# OptodeConnectors.net
KiCad netlist of a schematic drawn in Altium Designer
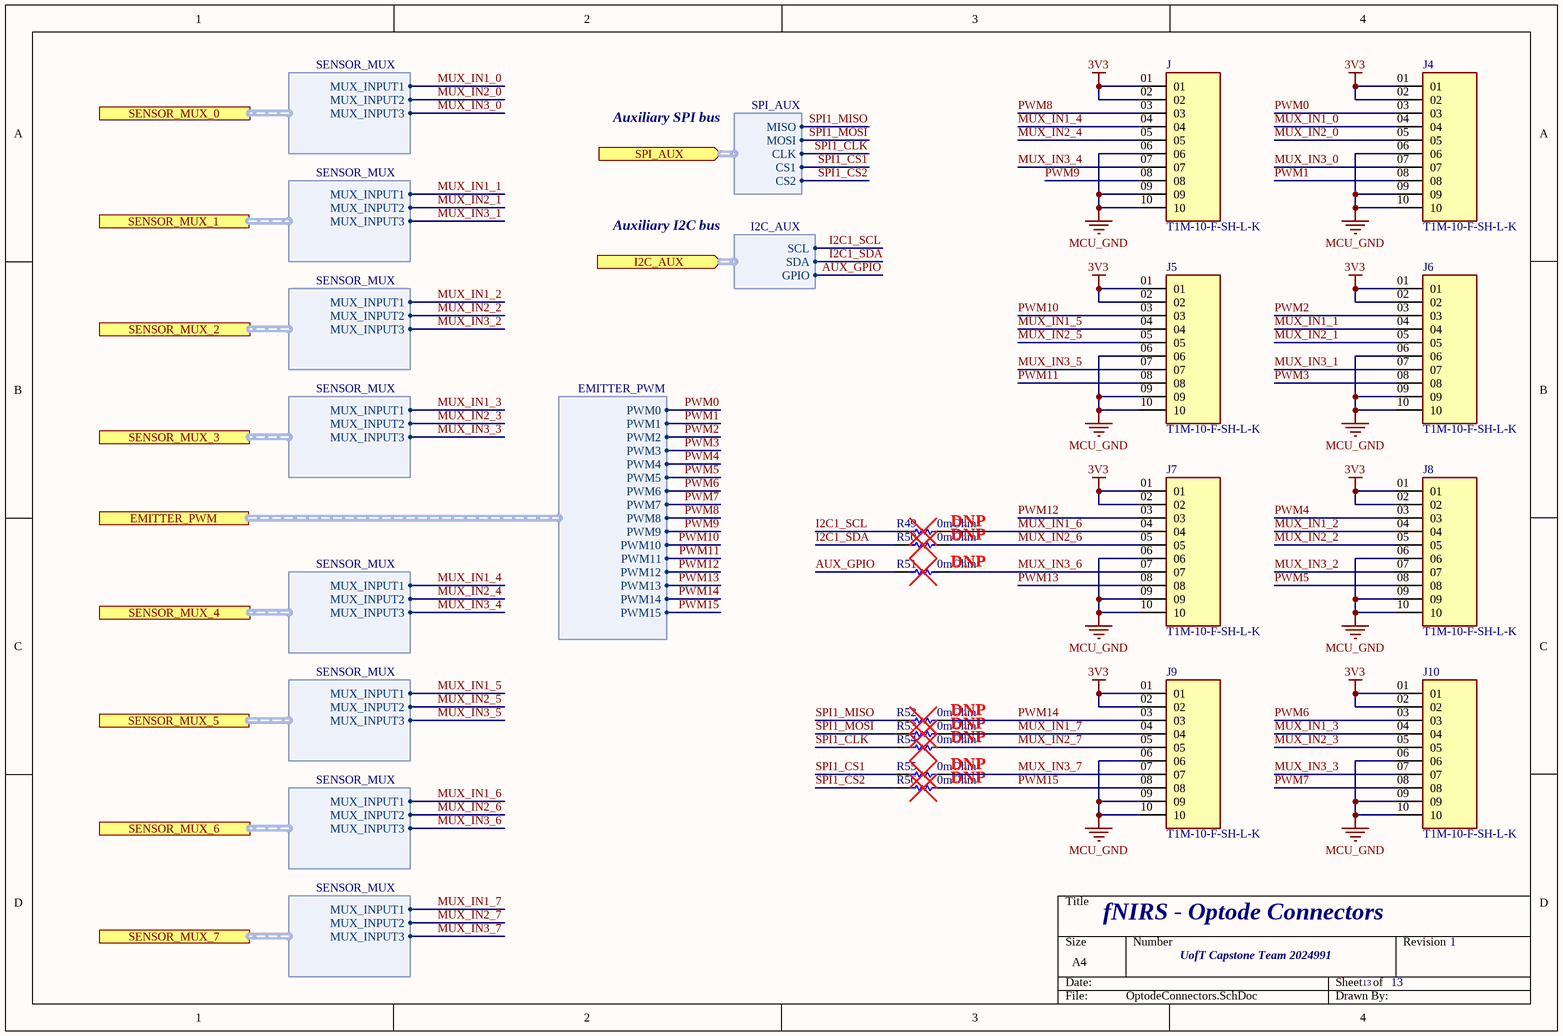
[diagram p0: OptodeConnectors.SchDoc]

(export (version "E")
  (design (tool "Eeschema 10.0.6"))
  (components
    (comp (ref "J")
      (value "T1M-10-F-SH-L-K")
      (footprint "SAMTEC_T1M-10-F-SH-L-K")
      (fields (field (name "MF") "Samtec"))
      (libsource (lib "Schlib2") (part "T1M-10-F-SH-L-K"))
    )
    (comp (ref "J4")
      (value "T1M-10-F-SH-L-K")
      (footprint "SAMTEC_T1M-10-F-SH-L-K")
      (fields (field (name "MF") "Samtec"))
      (libsource (lib "Schlib2") (part "T1M-10-F-SH-L-K"))
    )
    (comp (ref "J5")
      (value "T1M-10-F-SH-L-K")
      (footprint "SAMTEC_T1M-10-F-SH-L-K")
      (fields (field (name "MF") "Samtec"))
      (libsource (lib "Schlib2") (part "T1M-10-F-SH-L-K"))
    )
    (comp (ref "J6")
      (value "T1M-10-F-SH-L-K")
      (footprint "SAMTEC_T1M-10-F-SH-L-K")
      (fields (field (name "MF") "Samtec"))
      (libsource (lib "Schlib2") (part "T1M-10-F-SH-L-K"))
    )
    (comp (ref "J7")
      (value "T1M-10-F-SH-L-K")
      (footprint "SAMTEC_T1M-10-F-SH-L-K")
      (fields (field (name "MF") "Samtec"))
      (libsource (lib "Schlib2") (part "T1M-10-F-SH-L-K"))
    )
    (comp (ref "J8")
      (value "T1M-10-F-SH-L-K")
      (footprint "SAMTEC_T1M-10-F-SH-L-K")
      (fields (field (name "MF") "Samtec"))
      (libsource (lib "Schlib2") (part "T1M-10-F-SH-L-K"))
    )
    (comp (ref "J9")
      (value "T1M-10-F-SH-L-K")
      (footprint "SAMTEC_T1M-10-F-SH-L-K")
      (fields (field (name "MF") "Samtec"))
      (libsource (lib "Schlib2") (part "T1M-10-F-SH-L-K"))
    )
    (comp (ref "J10")
      (value "T1M-10-F-SH-L-K")
      (footprint "SAMTEC_T1M-10-F-SH-L-K")
      (fields (field (name "MF") "Samtec"))
      (libsource (lib "Schlib2") (part "T1M-10-F-SH-L-K"))
    )
    (comp (ref "R49")
      (value "RC0603JR-070RL")
      (footprint "RESC1608X55X25ML10T15")
      (description "Chip Resistor, 0 Ohm, +/- 5%, 0.1 W, -55 to 155 degC, 0603 (1608 Metric), RoHS, Tape and Reel")
      (fields
        (field (name "TOLERANCE") "5%")
        (field (name "RESISTANCE") "0mOhm")
        (field (name "MANUFACTURER") "Yageo")
      )
      (libsource (lib "Altium Content Vault") (part "RES-2"))
    )
    (comp (ref "R50")
      (value "RC0603JR-070RL")
      (footprint "RESC1608X55X25ML10T15")
      (description "Chip Resistor, 0 Ohm, +/- 5%, 0.1 W, -55 to 155 degC, 0603 (1608 Metric), RoHS, Tape and Reel")
      (fields
        (field (name "TOLERANCE") "5%")
        (field (name "RESISTANCE") "0mOhm")
        (field (name "MANUFACTURER") "Yageo")
      )
      (libsource (lib "Altium Content Vault") (part "RES-2"))
    )
    (comp (ref "R51")
      (value "RC0603JR-070RL")
      (footprint "RESC1608X55X25ML10T15")
      (description "Chip Resistor, 0 Ohm, +/- 5%, 0.1 W, -55 to 155 degC, 0603 (1608 Metric), RoHS, Tape and Reel")
      (fields
        (field (name "TOLERANCE") "5%")
        (field (name "RESISTANCE") "0mOhm")
        (field (name "MANUFACTURER") "Yageo")
      )
      (libsource (lib "Altium Content Vault") (part "RES-2"))
    )
    (comp (ref "R52")
      (value "RC0603JR-070RL")
      (footprint "RESC1608X55X25ML10T15")
      (description "Chip Resistor, 0 Ohm, +/- 5%, 0.1 W, -55 to 155 degC, 0603 (1608 Metric), RoHS, Tape and Reel")
      (fields
        (field (name "TOLERANCE") "5%")
        (field (name "RESISTANCE") "0mOhm")
        (field (name "MANUFACTURER") "Yageo")
      )
      (libsource (lib "Altium Content Vault") (part "RES-2"))
    )
    (comp (ref "R53")
      (value "RC0603JR-070RL")
      (footprint "RESC1608X55X25ML10T15")
      (description "Chip Resistor, 0 Ohm, +/- 5%, 0.1 W, -55 to 155 degC, 0603 (1608 Metric), RoHS, Tape and Reel")
      (fields
        (field (name "TOLERANCE") "5%")
        (field (name "RESISTANCE") "0mOhm")
        (field (name "MANUFACTURER") "Yageo")
      )
      (libsource (lib "Altium Content Vault") (part "RES-2"))
    )
    (comp (ref "R54")
      (value "RC0603JR-070RL")
      (footprint "RESC1608X55X25ML10T15")
      (description "Chip Resistor, 0 Ohm, +/- 5%, 0.1 W, -55 to 155 degC, 0603 (1608 Metric), RoHS, Tape and Reel")
      (fields
        (field (name "TOLERANCE") "5%")
        (field (name "RESISTANCE") "0mOhm")
        (field (name "MANUFACTURER") "Yageo")
      )
      (libsource (lib "Altium Content Vault") (part "RES-2"))
    )
    (comp (ref "R55")
      (value "RC0603JR-070RL")
      (footprint "RESC1608X55X25ML10T15")
      (description "Chip Resistor, 0 Ohm, +/- 5%, 0.1 W, -55 to 155 degC, 0603 (1608 Metric), RoHS, Tape and Reel")
      (fields
        (field (name "TOLERANCE") "5%")
        (field (name "RESISTANCE") "0mOhm")
        (field (name "MANUFACTURER") "Yageo")
      )
      (libsource (lib "Altium Content Vault") (part "RES-2"))
    )
    (comp (ref "R56")
      (value "RC0603JR-070RL")
      (footprint "RESC1608X55X25ML10T15")
      (description "Chip Resistor, 0 Ohm, +/- 5%, 0.1 W, -55 to 155 degC, 0603 (1608 Metric), RoHS, Tape and Reel")
      (fields
        (field (name "TOLERANCE") "5%")
        (field (name "RESISTANCE") "0mOhm")
        (field (name "MANUFACTURER") "Yageo")
      )
      (libsource (lib "Altium Content Vault") (part "RES-2"))
    )
  )
  (nets
    (net (code "5") (name "/AUX_GPIO") (class "Default")
      (node (ref "R51") (pin "2") (pinfunction "2_2") (pintype "passive"))
    )
    (net (code "6") (name "/I2C1_SCL") (class "Default")
      (node (ref "R49") (pin "2") (pinfunction "2_2") (pintype "passive"))
    )
    (net (code "7") (name "/I2C1_SDA") (class "Default")
      (node (ref "R50") (pin "2") (pinfunction "2_2") (pintype "passive"))
    )
    (net (code "8") (name "/MUX_IN1_0") (class "Default")
      (node (ref "J4") (pin "04") (pinfunction "04_04") (pintype "passive"))
    )
    (net (code "9") (name "/MUX_IN1_1") (class "Default")
      (node (ref "J6") (pin "04") (pinfunction "04_04") (pintype "passive"))
    )
    (net (code "10") (name "/MUX_IN1_2") (class "Default")
      (node (ref "J8") (pin "04") (pinfunction "04_04") (pintype "passive"))
    )
    (net (code "11") (name "/MUX_IN1_3") (class "Default")
      (node (ref "J10") (pin "04") (pinfunction "04_04") (pintype "passive"))
    )
    (net (code "12") (name "/MUX_IN1_4") (class "Default")
      (node (ref "J") (pin "04") (pinfunction "04_04") (pintype "passive"))
    )
    (net (code "13") (name "/MUX_IN1_5") (class "Default")
      (node (ref "J5") (pin "04") (pinfunction "04_04") (pintype "passive"))
    )
    (net (code "14") (name "/MUX_IN1_6") (class "Default")
      (node (ref "J7") (pin "04") (pinfunction "04_04") (pintype "passive"))
      (node (ref "R49") (pin "1") (pinfunction "1_1") (pintype "passive"))
    )
    (net (code "15") (name "/MUX_IN1_7") (class "Default")
      (node (ref "J9") (pin "04") (pinfunction "04_04") (pintype "passive"))
      (node (ref "R53") (pin "1") (pinfunction "1_1") (pintype "passive"))
    )
    (net (code "16") (name "/MUX_IN2_0") (class "Default")
      (node (ref "J4") (pin "05") (pinfunction "05_05") (pintype "passive"))
    )
    (net (code "17") (name "/MUX_IN2_1") (class "Default")
      (node (ref "J6") (pin "05") (pinfunction "05_05") (pintype "passive"))
    )
    (net (code "18") (name "/MUX_IN2_2") (class "Default")
      (node (ref "J8") (pin "05") (pinfunction "05_05") (pintype "passive"))
    )
    (net (code "19") (name "/MUX_IN2_3") (class "Default")
      (node (ref "J10") (pin "05") (pinfunction "05_05") (pintype "passive"))
    )
    (net (code "20") (name "/MUX_IN2_4") (class "Default")
      (node (ref "J") (pin "05") (pinfunction "05_05") (pintype "passive"))
    )
    (net (code "21") (name "/MUX_IN2_5") (class "Default")
      (node (ref "J5") (pin "05") (pinfunction "05_05") (pintype "passive"))
    )
    (net (code "22") (name "/MUX_IN2_6") (class "Default")
      (node (ref "J7") (pin "05") (pinfunction "05_05") (pintype "passive"))
      (node (ref "R50") (pin "1") (pinfunction "1_1") (pintype "passive"))
    )
    (net (code "23") (name "/MUX_IN2_7") (class "Default")
      (node (ref "J9") (pin "05") (pinfunction "05_05") (pintype "passive"))
      (node (ref "R54") (pin "1") (pinfunction "1_1") (pintype "passive"))
    )
    (net (code "24") (name "/MUX_IN3_0") (class "Default")
      (node (ref "J4") (pin "07") (pinfunction "07_07") (pintype "passive"))
    )
    (net (code "25") (name "/MUX_IN3_1") (class "Default")
      (node (ref "J6") (pin "07") (pinfunction "07_07") (pintype "passive"))
    )
    (net (code "26") (name "/MUX_IN3_2") (class "Default")
      (node (ref "J8") (pin "07") (pinfunction "07_07") (pintype "passive"))
    )
    (net (code "27") (name "/MUX_IN3_3") (class "Default")
      (node (ref "J10") (pin "07") (pinfunction "07_07") (pintype "passive"))
    )
    (net (code "28") (name "/MUX_IN3_4") (class "Default")
      (node (ref "J") (pin "07") (pinfunction "07_07") (pintype "passive"))
    )
    (net (code "29") (name "/MUX_IN3_5") (class "Default")
      (node (ref "J5") (pin "07") (pinfunction "07_07") (pintype "passive"))
    )
    (net (code "30") (name "/MUX_IN3_6") (class "Default")
      (node (ref "J7") (pin "07") (pinfunction "07_07") (pintype "passive"))
      (node (ref "R51") (pin "1") (pinfunction "1_1") (pintype "passive"))
    )
    (net (code "31") (name "/MUX_IN3_7") (class "Default")
      (node (ref "J9") (pin "07") (pinfunction "07_07") (pintype "passive"))
      (node (ref "R55") (pin "1") (pinfunction "1_1") (pintype "passive"))
    )
    (net (code "32") (name "/PWM0") (class "Default")
      (node (ref "J4") (pin "03") (pinfunction "03_03") (pintype "passive"))
    )
    (net (code "33") (name "/PWM1") (class "Default")
      (node (ref "J4") (pin "08") (pinfunction "08_08") (pintype "passive"))
    )
    (net (code "34") (name "/PWM2") (class "Default")
      (node (ref "J6") (pin "03") (pinfunction "03_03") (pintype "passive"))
    )
    (net (code "35") (name "/PWM3") (class "Default")
      (node (ref "J6") (pin "08") (pinfunction "08_08") (pintype "passive"))
    )
    (net (code "36") (name "/PWM4") (class "Default")
      (node (ref "J8") (pin "03") (pinfunction "03_03") (pintype "passive"))
    )
    (net (code "37") (name "/PWM5") (class "Default")
      (node (ref "J8") (pin "08") (pinfunction "08_08") (pintype "passive"))
    )
    (net (code "38") (name "/PWM6") (class "Default")
      (node (ref "J10") (pin "03") (pinfunction "03_03") (pintype "passive"))
    )
    (net (code "39") (name "/PWM7") (class "Default")
      (node (ref "J10") (pin "08") (pinfunction "08_08") (pintype "passive"))
    )
    (net (code "40") (name "/PWM8") (class "Default")
      (node (ref "J") (pin "03") (pinfunction "03_03") (pintype "passive"))
    )
    (net (code "41") (name "/PWM9") (class "Default")
      (node (ref "J") (pin "08") (pinfunction "08_08") (pintype "passive"))
    )
    (net (code "42") (name "/PWM10") (class "Default")
      (node (ref "J5") (pin "03") (pinfunction "03_03") (pintype "passive"))
    )
    (net (code "43") (name "/PWM11") (class "Default")
      (node (ref "J5") (pin "08") (pinfunction "08_08") (pintype "passive"))
    )
    (net (code "44") (name "/PWM12") (class "Default")
      (node (ref "J7") (pin "03") (pinfunction "03_03") (pintype "passive"))
    )
    (net (code "45") (name "/PWM13") (class "Default")
      (node (ref "J7") (pin "08") (pinfunction "08_08") (pintype "passive"))
    )
    (net (code "46") (name "/PWM14") (class "Default")
      (node (ref "J9") (pin "03") (pinfunction "03_03") (pintype "passive"))
      (node (ref "R52") (pin "1") (pinfunction "1_1") (pintype "passive"))
    )
    (net (code "47") (name "/PWM15") (class "Default")
      (node (ref "J9") (pin "08") (pinfunction "08_08") (pintype "passive"))
      (node (ref "R56") (pin "1") (pinfunction "1_1") (pintype "passive"))
    )
    (net (code "48") (name "/SPI1_CLK") (class "Default")
      (node (ref "R54") (pin "2") (pinfunction "2_2") (pintype "passive"))
    )
    (net (code "49") (name "/SPI1_CS1") (class "Default")
      (node (ref "R55") (pin "2") (pinfunction "2_2") (pintype "passive"))
    )
    (net (code "50") (name "/SPI1_CS2") (class "Default")
      (node (ref "R56") (pin "2") (pinfunction "2_2") (pintype "passive"))
    )
    (net (code "51") (name "/SPI1_MISO") (class "Default")
      (node (ref "R52") (pin "2") (pinfunction "2_2") (pintype "passive"))
    )
    (net (code "52") (name "/SPI1_MOSI") (class "Default")
      (node (ref "R53") (pin "2") (pinfunction "2_2") (pintype "passive"))
    )
    (net (code "57") (name "3V3") (class "Default")
      (node (ref "J") (pin "01") (pinfunction "01_01") (pintype "passive"))
      (node (ref "J") (pin "02") (pinfunction "02_02") (pintype "passive"))
      (node (ref "J10") (pin "01") (pinfunction "01_01") (pintype "passive"))
      (node (ref "J10") (pin "02") (pinfunction "02_02") (pintype "passive"))
      (node (ref "J4") (pin "01") (pinfunction "01_01") (pintype "passive"))
      (node (ref "J4") (pin "02") (pinfunction "02_02") (pintype "passive"))
      (node (ref "J5") (pin "01") (pinfunction "01_01") (pintype "passive"))
      (node (ref "J5") (pin "02") (pinfunction "02_02") (pintype "passive"))
      (node (ref "J6") (pin "01") (pinfunction "01_01") (pintype "passive"))
      (node (ref "J6") (pin "02") (pinfunction "02_02") (pintype "passive"))
      (node (ref "J7") (pin "01") (pinfunction "01_01") (pintype "passive"))
      (node (ref "J7") (pin "02") (pinfunction "02_02") (pintype "passive"))
      (node (ref "J8") (pin "01") (pinfunction "01_01") (pintype "passive"))
      (node (ref "J8") (pin "02") (pinfunction "02_02") (pintype "passive"))
      (node (ref "J9") (pin "01") (pinfunction "01_01") (pintype "passive"))
      (node (ref "J9") (pin "02") (pinfunction "02_02") (pintype "passive"))
    )
    (net (code "58") (name "MCU_GND") (class "Default")
      (node (ref "J") (pin "06") (pinfunction "06_06") (pintype "passive"))
      (node (ref "J") (pin "09") (pinfunction "09_09") (pintype "passive"))
      (node (ref "J") (pin "10") (pinfunction "10_10") (pintype "passive"))
      (node (ref "J10") (pin "06") (pinfunction "06_06") (pintype "passive"))
      (node (ref "J10") (pin "09") (pinfunction "09_09") (pintype "passive"))
      (node (ref "J10") (pin "10") (pinfunction "10_10") (pintype "passive"))
      (node (ref "J4") (pin "06") (pinfunction "06_06") (pintype "passive"))
      (node (ref "J4") (pin "09") (pinfunction "09_09") (pintype "passive"))
      (node (ref "J4") (pin "10") (pinfunction "10_10") (pintype "passive"))
      (node (ref "J5") (pin "06") (pinfunction "06_06") (pintype "passive"))
      (node (ref "J5") (pin "09") (pinfunction "09_09") (pintype "passive"))
      (node (ref "J5") (pin "10") (pinfunction "10_10") (pintype "passive"))
      (node (ref "J6") (pin "06") (pinfunction "06_06") (pintype "passive"))
      (node (ref "J6") (pin "09") (pinfunction "09_09") (pintype "passive"))
      (node (ref "J6") (pin "10") (pinfunction "10_10") (pintype "passive"))
      (node (ref "J7") (pin "06") (pinfunction "06_06") (pintype "passive"))
      (node (ref "J7") (pin "09") (pinfunction "09_09") (pintype "passive"))
      (node (ref "J7") (pin "10") (pinfunction "10_10") (pintype "passive"))
      (node (ref "J8") (pin "06") (pinfunction "06_06") (pintype "passive"))
      (node (ref "J8") (pin "09") (pinfunction "09_09") (pintype "passive"))
      (node (ref "J8") (pin "10") (pinfunction "10_10") (pintype "passive"))
      (node (ref "J9") (pin "06") (pinfunction "06_06") (pintype "passive"))
      (node (ref "J9") (pin "09") (pinfunction "09_09") (pintype "passive"))
      (node (ref "J9") (pin "10") (pinfunction "10_10") (pintype "passive"))
    )
  )
)
